# DRV8701_V2_0.net
KiCad netlist of a schematic drawn in EasyEDA Pro
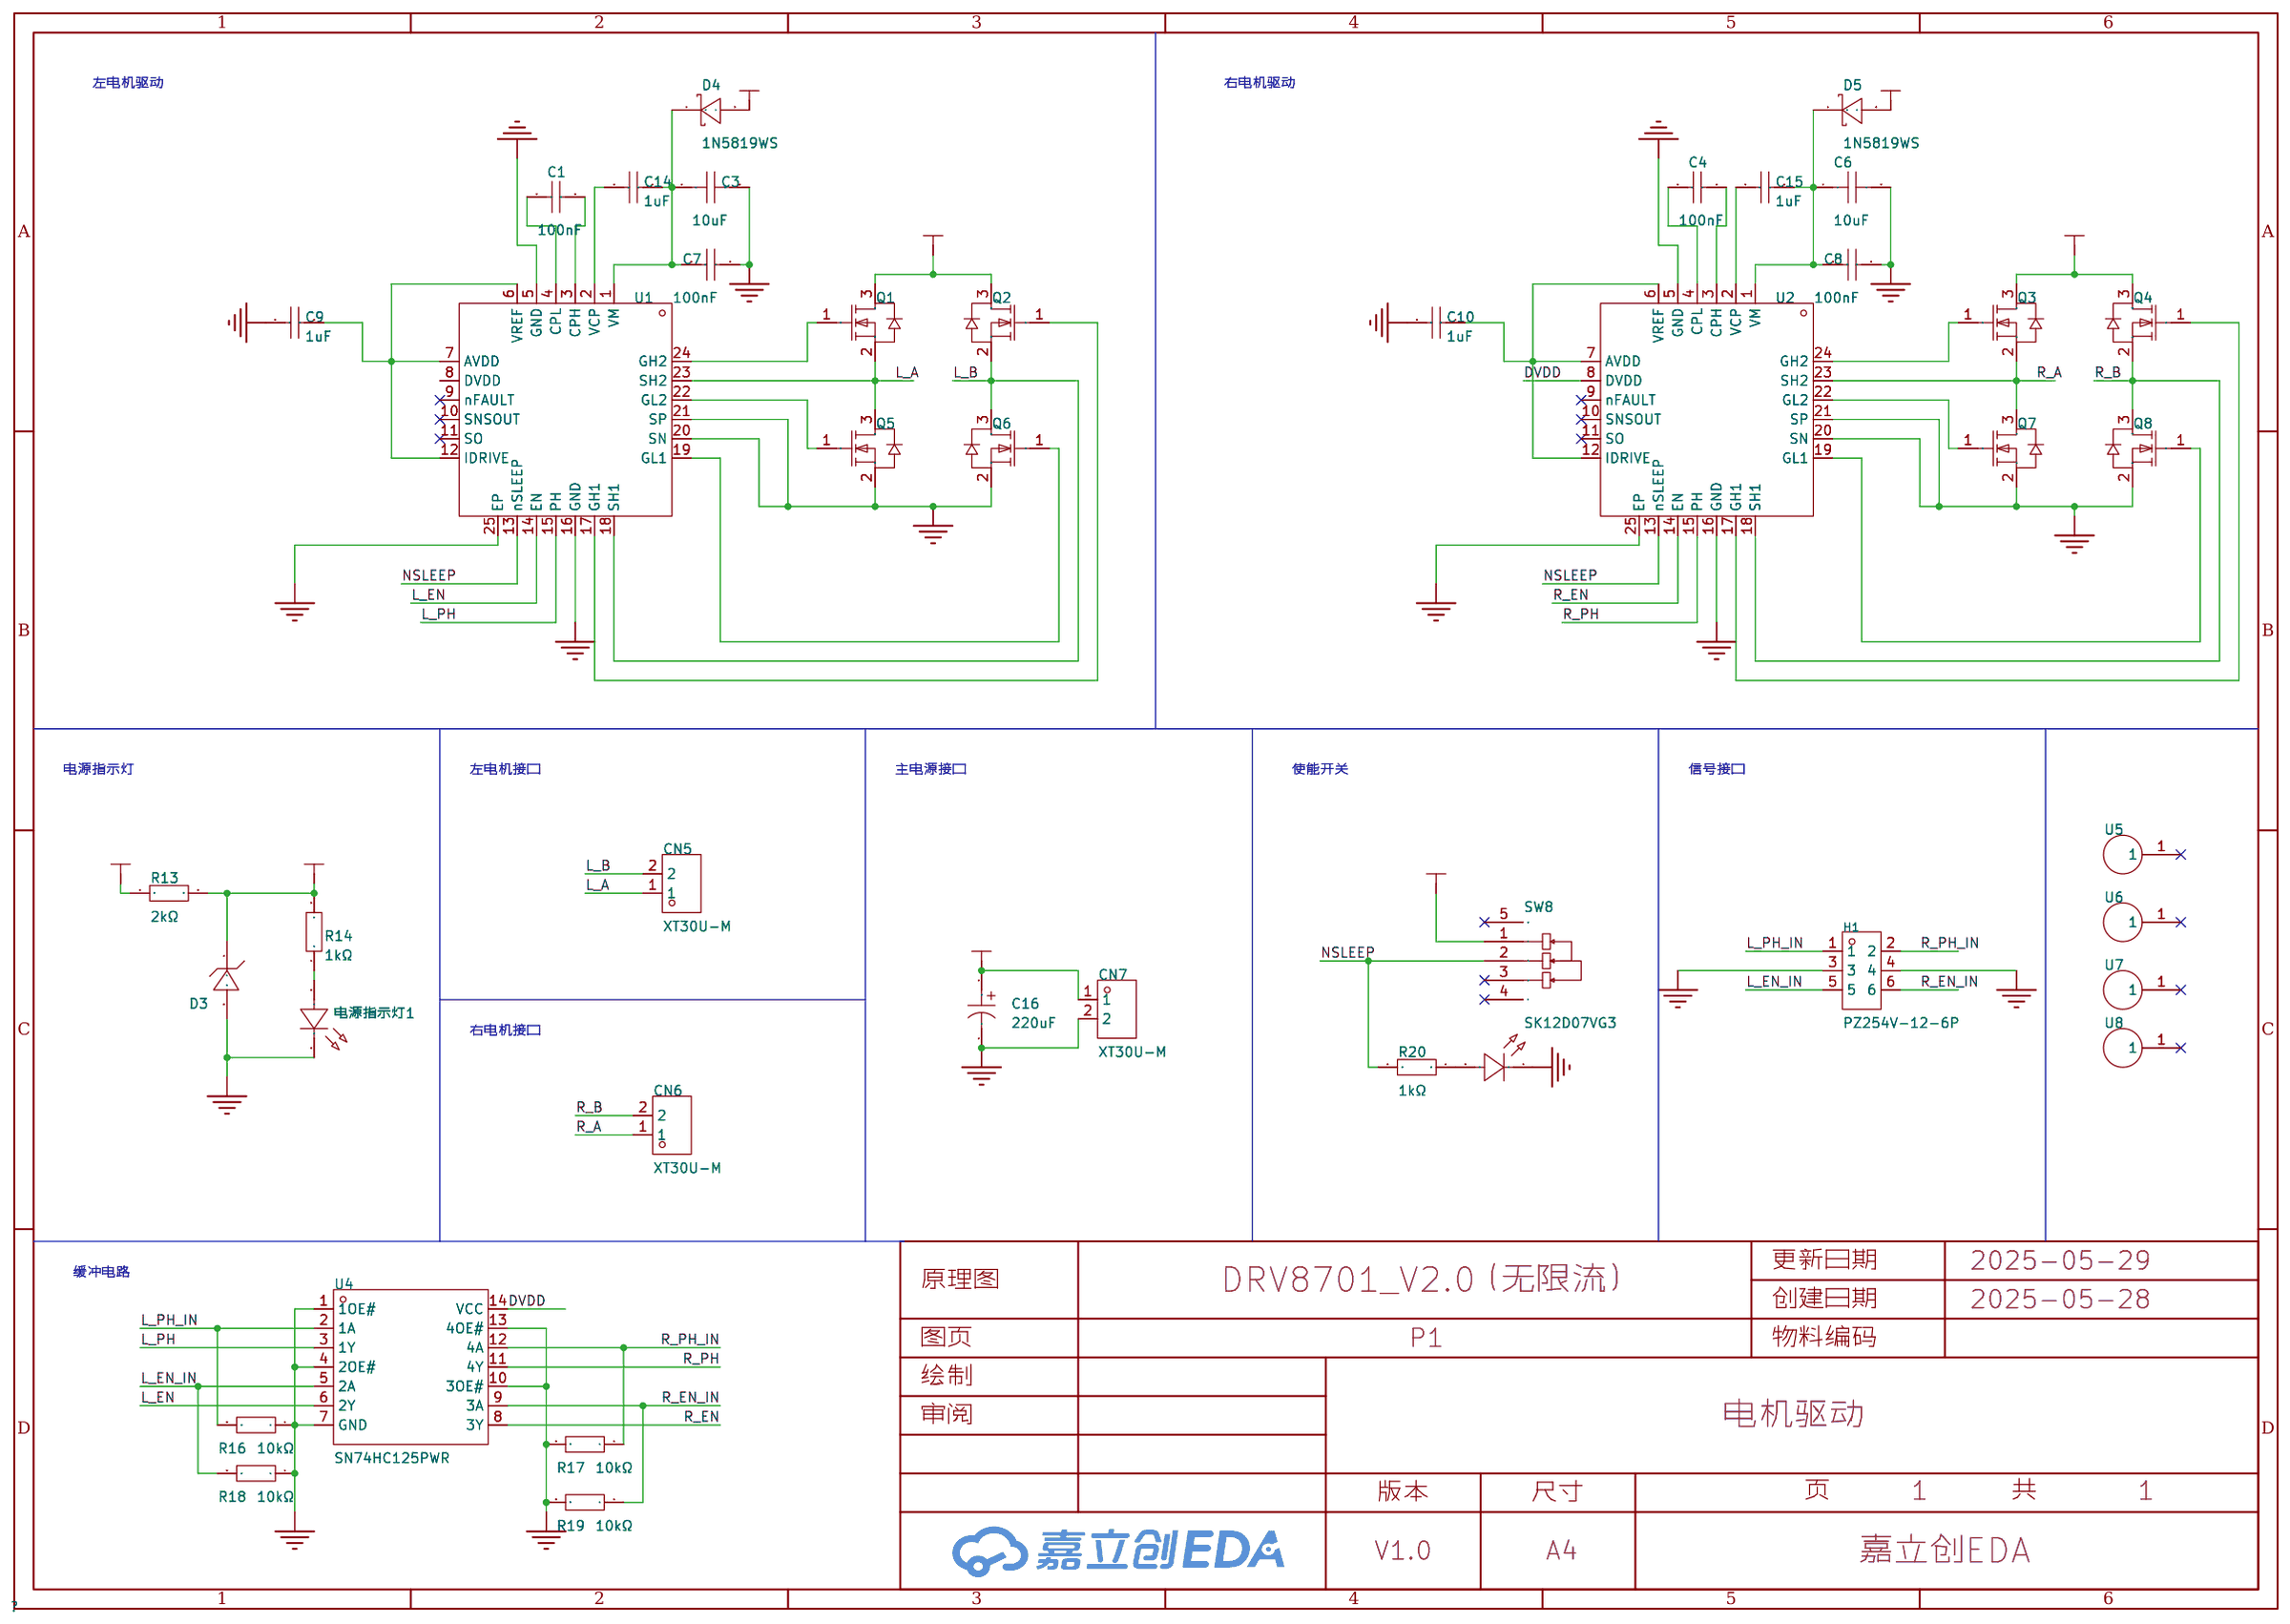
[diagram p0: schematic sheet]

(export (version "E")
  (design (tool "Eeschema 10.0.6"))
  (components
    (comp (ref "C1")
      (value "100nF")
      (footprint "easyedapro:C0603")
      (description "容值:100nF;精度:±10%;额定电压:16V;材质(温度系数):X7R;")
      (fields
        (field (name "Manufacturer Part") "CL10B104KO8NNNC")
        (field (name "Manufacturer") "SAMSUNG(三星)")
      )
      (libsource (lib "easyedapro") (part "CL10B104KO8NNNC"))
    )
    (comp (ref "C3")
      (value "10uF")
      (footprint "easyedapro:C0603")
      (description "容值:10uF;精度:±20%;额定电压:25V;材质(温度系数):X5R;")
      (fields
        (field (name "Manufacturer Part") "CL10A106MA8NRNC")
        (field (name "Manufacturer") "SAMSUNG(三星)")
      )
      (libsource (lib "easyedapro") (part "CL10A106MA8NRNC"))
    )
    (comp (ref "C4")
      (value "100nF")
      (footprint "easyedapro:C0603")
      (description "容值:100nF;精度:±10%;额定电压:16V;材质(温度系数):X7R;")
      (fields
        (field (name "Manufacturer Part") "CL10B104KO8NNNC")
        (field (name "Manufacturer") "SAMSUNG(三星)")
      )
      (libsource (lib "easyedapro") (part "CL10B104KO8NNNC"))
    )
    (comp (ref "C6")
      (value "10uF")
      (footprint "easyedapro:C0603")
      (description "容值:10uF;精度:±20%;额定电压:25V;材质(温度系数):X5R;")
      (fields
        (field (name "Manufacturer Part") "CL10A106MA8NRNC")
        (field (name "Manufacturer") "SAMSUNG(三星)")
      )
      (libsource (lib "easyedapro") (part "CL10A106MA8NRNC"))
    )
    (comp (ref "C7")
      (value "100nF")
      (footprint "easyedapro:C0603")
      (description "容值:100nF;精度:±10%;额定电压:16V;材质(温度系数):X7R;")
      (fields
        (field (name "Manufacturer Part") "CL10B104KO8NNNC")
        (field (name "Manufacturer") "SAMSUNG(三星)")
      )
      (libsource (lib "easyedapro") (part "CL10B104KO8NNNC"))
    )
    (comp (ref "C8")
      (value "100nF")
      (footprint "easyedapro:C0603")
      (description "容值:100nF;精度:±10%;额定电压:16V;材质(温度系数):X7R;")
      (fields
        (field (name "Manufacturer Part") "CL10B104KO8NNNC")
        (field (name "Manufacturer") "SAMSUNG(三星)")
      )
      (libsource (lib "easyedapro") (part "CL10B104KO8NNNC"))
    )
    (comp (ref "C9")
      (value "1uF")
      (footprint "easyedapro:C0603")
      (description "容值:1uF;精度:±10%;额定电压:25V;材质(温度系数):X7R;")
      (fields
        (field (name "Manufacturer Part") "CL10B105KA8NNNC")
        (field (name "Manufacturer") "SAMSUNG(三星)")
      )
      (libsource (lib "easyedapro") (part "CL10B105KA8NNNC"))
    )
    (comp (ref "C10")
      (value "1uF")
      (footprint "easyedapro:C0603")
      (description "容值:1uF;精度:±10%;额定电压:25V;材质(温度系数):X7R;")
      (fields
        (field (name "Manufacturer Part") "CL10B105KA8NNNC")
        (field (name "Manufacturer") "SAMSUNG(三星)")
      )
      (libsource (lib "easyedapro") (part "CL10B105KA8NNNC"))
    )
    (comp (ref "C14")
      (value "1uF")
      (footprint "easyedapro:C0603")
      (description "容值:1uF;精度:±10%;额定电压:25V;材质(温度系数):X7R;")
      (fields
        (field (name "Manufacturer Part") "CL10B105KA8NNNC")
        (field (name "Manufacturer") "SAMSUNG(三星)")
      )
      (libsource (lib "easyedapro") (part "CL10B105KA8NNNC"))
    )
    (comp (ref "C15")
      (value "1uF")
      (footprint "easyedapro:C0603")
      (description "容值:1uF;精度:±10%;额定电压:25V;材质(温度系数):X7R;")
      (fields
        (field (name "Manufacturer Part") "CL10B105KA8NNNC")
        (field (name "Manufacturer") "SAMSUNG(三星)")
      )
      (libsource (lib "easyedapro") (part "CL10B105KA8NNNC"))
    )
    (comp (ref "C16")
      (value "220uF")
      (footprint "easyedapro:CAP-TH_BD6.3-P2.50-D0.5-FD")
      (description "容值:220uF;精度:±20%;额定电压:25V;纹波电流:400mA@100kHz;等效串联电阻:180mΩ@100kHz;")
      (fields (field (name "Manufacturer Part") "03EC0593") (field (name "Manufacturer") "KNSCHA(科尼盛)"))
      (libsource (lib "easyedapro") (part "03EC0593"))
    )
    (comp (ref "CN5")
      (value "XT30U-M")
      (footprint "easyedapro:CONN-TH_XT30U-M")
      (description "类别:-;类型1:-;")
      (fields (field (name "Manufacturer") "AMASS(艾迈斯)"))
      (libsource (lib "easyedapro") (part "XT30U-M"))
    )
    (comp (ref "CN6")
      (value "XT30U-M")
      (footprint "easyedapro:CONN-TH_XT30U-M")
      (description "类别:-;类型1:-;")
      (fields (field (name "Manufacturer") "AMASS(艾迈斯)"))
      (libsource (lib "easyedapro") (part "XT30U-M"))
    )
    (comp (ref "CN7")
      (value "XT30U-M")
      (footprint "easyedapro:CONN-TH_XT30U-M")
      (description "类别:-;类型1:-;")
      (fields (field (name "Manufacturer") "AMASS(艾迈斯)"))
      (libsource (lib "easyedapro") (part "XT30U-M"))
    )
    (comp (ref "D3")
      (value "BZT52C3V3-7-F")
      (footprint "easyedapro:SOD-123_L2.7-W1.6-LS3.7-RD")
      (description "二极管配置:独立式;稳压值(标称值):3.3V;稳压值(范围):3.1V~3.5V;功率:500mW;精度:±6%;")
      (fields (field (name "Manufacturer") "DIODES(美台)"))
      (libsource (lib "easyedapro") (part "BZT52C3V3-7-F"))
    )
    (comp (ref "D4")
      (value "1N5819WS")
      (footprint "easyedapro:SOD-323_L1.8-W1.3-LS2.5-RD")
      (description "正向压降(Vf):600mV@1A;直流反向耐压(Vr):40V;整流电流:1A;")
      (fields (field (name "Manufacturer") "Hottech(合科泰)"))
      (libsource (lib "easyedapro") (part "1N5819WS"))
    )
    (comp (ref "D5")
      (value "1N5819WS")
      (footprint "easyedapro:SOD-323_L1.8-W1.3-LS2.5-RD")
      (description "正向压降(Vf):600mV@1A;直流反向耐压(Vr):40V;整流电流:1A;")
      (fields (field (name "Manufacturer") "Hottech(合科泰)"))
      (libsource (lib "easyedapro") (part "1N5819WS"))
    )
    (comp (ref "H1")
      (value "PZ254V-12-6P")
      (footprint "easyedapro:HDR-TH_6P-P2.54-V-M-R2-C3-S2.54")
      (fields (field (name "Manufacturer") "XFCN(兴飞)"))
      (libsource (lib "easyedapro") (part "PZ254V-12-6P"))
    )
    (comp (ref "Q1")
      (value "2N7002")
      (footprint "easyedapro:DSOP-8_L5.0-W5.0-P1.27-LS6.0-BL-EP（rebuild）")
      (fields (field (name "Manufacturer") "CJ(江苏长电/长晶)"))
      (libsource (lib "easyedapro") (part "TPH1R403NL(rebuild)"))
    )
    (comp (ref "Q2")
      (value "2N7002")
      (footprint "easyedapro:DSOP-8_L5.0-W5.0-P1.27-LS6.0-BL-EP（rebuild）")
      (fields (field (name "Manufacturer") "CJ(江苏长电/长晶)"))
      (libsource (lib "easyedapro") (part "TPH1R403NL(rebuild)"))
    )
    (comp (ref "Q3")
      (value "2N7002")
      (footprint "easyedapro:DSOP-8_L5.0-W5.0-P1.27-LS6.0-BL-EP（rebuild）")
      (fields (field (name "Manufacturer") "CJ(江苏长电/长晶)"))
      (libsource (lib "easyedapro") (part "TPH1R403NL(rebuild)"))
    )
    (comp (ref "Q4")
      (value "2N7002")
      (footprint "easyedapro:DSOP-8_L5.0-W5.0-P1.27-LS6.0-BL-EP（rebuild）")
      (fields (field (name "Manufacturer") "CJ(江苏长电/长晶)"))
      (libsource (lib "easyedapro") (part "TPH1R403NL(rebuild)"))
    )
    (comp (ref "Q5")
      (value "2N7002")
      (footprint "easyedapro:DSOP-8_L5.0-W5.0-P1.27-LS6.0-BL-EP（rebuild）")
      (fields (field (name "Manufacturer") "CJ(江苏长电/长晶)"))
      (libsource (lib "easyedapro") (part "TPH1R403NL(rebuild)"))
    )
    (comp (ref "Q6")
      (value "2N7002")
      (footprint "easyedapro:DSOP-8_L5.0-W5.0-P1.27-LS6.0-BL-EP（rebuild）")
      (fields (field (name "Manufacturer") "CJ(江苏长电/长晶)"))
      (libsource (lib "easyedapro") (part "TPH1R403NL(rebuild)"))
    )
    (comp (ref "Q7")
      (value "2N7002")
      (footprint "easyedapro:DSOP-8_L5.0-W5.0-P1.27-LS6.0-BL-EP（rebuild）")
      (fields (field (name "Manufacturer") "CJ(江苏长电/长晶)"))
      (libsource (lib "easyedapro") (part "TPH1R403NL(rebuild)"))
    )
    (comp (ref "Q8")
      (value "2N7002")
      (footprint "easyedapro:DSOP-8_L5.0-W5.0-P1.27-LS6.0-BL-EP（rebuild）")
      (fields (field (name "Manufacturer") "CJ(江苏长电/长晶)"))
      (libsource (lib "easyedapro") (part "TPH1R403NL(rebuild)"))
    )
    (comp (ref "R13")
      (value "2kΩ")
      (footprint "easyedapro:R0603")
      (description "电阻类型:厚膜电阻;阻值:2.2kΩ;精度:±1%;功率:100mW;最大工作电压:75V;温度系数:±100ppm/°C;")
      (fields
        (field (name "Manufacturer Part") "0603WAF2201T5E")
        (field (name "Manufacturer") "UNI-ROYAL(厚声)")
      )
      (libsource (lib "easyedapro") (part "0603WAF2201T5E"))
    )
    (comp (ref "R14")
      (value "1kΩ")
      (footprint "easyedapro:R0603")
      (description "电阻类型:厚膜电阻;阻值:1kΩ;精度:±1%;功率:100mW;最大工作电压:75V;温度系数:±100ppm/°C;")
      (fields
        (field (name "Manufacturer Part") "0603WAF1001T5E")
        (field (name "Manufacturer") "UNI-ROYAL(厚声)")
      )
      (libsource (lib "easyedapro") (part "0603WAF1001T5E"))
    )
    (comp (ref "R16")
      (value "10kΩ")
      (footprint "easyedapro:R0603")
      (description "电阻类型:厚膜电阻;阻值:10kΩ;精度:±1%;功率:100mW;最大工作电压:75V;温度系数:±100ppm/°C;")
      (fields
        (field (name "Manufacturer Part") "0603WAF1002T5E")
        (field (name "Manufacturer") "UNI-ROYAL(厚声)")
      )
      (libsource (lib "easyedapro") (part "0603WAF1002T5E"))
    )
    (comp (ref "R17")
      (value "10kΩ")
      (footprint "easyedapro:R0603")
      (description "电阻类型:厚膜电阻;阻值:10kΩ;精度:±1%;功率:100mW;最大工作电压:75V;温度系数:±100ppm/°C;")
      (fields
        (field (name "Manufacturer Part") "0603WAF1002T5E")
        (field (name "Manufacturer") "UNI-ROYAL(厚声)")
      )
      (libsource (lib "easyedapro") (part "0603WAF1002T5E"))
    )
    (comp (ref "R18")
      (value "10kΩ")
      (footprint "easyedapro:R0603")
      (description "电阻类型:厚膜电阻;阻值:10kΩ;精度:±1%;功率:100mW;最大工作电压:75V;温度系数:±100ppm/°C;")
      (fields
        (field (name "Manufacturer Part") "0603WAF1002T5E")
        (field (name "Manufacturer") "UNI-ROYAL(厚声)")
      )
      (libsource (lib "easyedapro") (part "0603WAF1002T5E"))
    )
    (comp (ref "R19")
      (value "10kΩ")
      (footprint "easyedapro:R0603")
      (description "电阻类型:厚膜电阻;阻值:10kΩ;精度:±1%;功率:100mW;最大工作电压:75V;温度系数:±100ppm/°C;")
      (fields
        (field (name "Manufacturer Part") "0603WAF1002T5E")
        (field (name "Manufacturer") "UNI-ROYAL(厚声)")
      )
      (libsource (lib "easyedapro") (part "0603WAF1002T5E"))
    )
    (comp (ref "R20")
      (value "1kΩ")
      (footprint "easyedapro:R0603")
      (description "电阻类型:厚膜电阻;阻值:1kΩ;精度:±1%;功率:100mW;最大工作电压:75V;温度系数:±100ppm/°C;")
      (fields
        (field (name "Manufacturer Part") "0603WAF1001T5E")
        (field (name "Manufacturer") "UNI-ROYAL(厚声)")
      )
      (libsource (lib "easyedapro") (part "0603WAF1001T5E"))
    )
    (comp (ref "SW8")
      (value "SK12D07VG3")
      (footprint "easyedapro:SW-TH_SK12D07VG3")
      (description "电路结构:单刀双掷;安装方式:侧插;开关颜色:-;额定电流(DC):500mA;额定电压(DC):50V;额定电流(AC):-;额定电压(AC):-;机械寿命:5千次;")
      (fields (field (name "Manufacturer") "SHOU HAN(首韩)"))
      (libsource (lib "easyedapro") (part "SK12D07VG3_C431547"))
    )
    (comp (ref "U1")
      (value "DRV8701ERGET")
      (footprint "easyedapro:VQFN-24_L4.0-W4.0-P0.50-BL-EP2.5")
      (description "DRV8701 47V H 桥智能栅极驱动器")
      (fields (field (name "Manufacturer") "TI(德州仪器)"))
      (libsource (lib "easyedapro") (part "DRV8701ERGET"))
    )
    (comp (ref "U2")
      (value "DRV8701ERGET")
      (footprint "easyedapro:VQFN-24_L4.0-W4.0-P0.50-BL-EP2.5")
      (description "DRV8701 47V H 桥智能栅极驱动器")
      (fields (field (name "Manufacturer") "TI(德州仪器)"))
      (libsource (lib "easyedapro") (part "DRV8701ERGET"))
    )
    (comp (ref "U4")
      (value "SN74HC125PWR")
      (footprint "easyedapro:TSSOP-14_L5.0-W4.4-P0.65-LS6.5-BL")
      (description "输入类型:-;电源电压:2V~6V;元件数:4;每个元件位数:1;灌电流(IOL):7.8mA;拉电流(IOH):7.8mA;")
      (fields (field (name "Manufacturer") "TI(德州仪器)"))
      (libsource (lib "easyedapro") (part "SN74HC125PWR"))
    )
    (comp (ref "U5") (value "~") (footprint "easyedapro:M3螺丝孔") (libsource (lib "easyedapro") (part "M3螺丝孔")))
    (comp (ref "U6") (value "~") (footprint "easyedapro:M3螺丝孔") (libsource (lib "easyedapro") (part "M3螺丝孔")))
    (comp (ref "U7") (value "~") (footprint "easyedapro:M3螺丝孔") (libsource (lib "easyedapro") (part "M3螺丝孔")))
    (comp (ref "U8") (value "~") (footprint "easyedapro:M3螺丝孔") (libsource (lib "easyedapro") (part "M3螺丝孔")))
    (comp (ref "电源指示灯1")
      (value "XL-1608SURC-06")
      (footprint "easyedapro:LED0603-RD_RED")
      (description "发光颜色:红色;功率:55mW;正向电流:25mA;主波长:617nm~621nm;透镜颜色:无色透明透镜;色温:-;发光角度:120°;载带方式:正贴;工作温度:-30°C~+85°C;")
      (fields (field (name "Manufacturer") "XINGLIGHT(成兴光)"))
      (libsource (lib "easyedapro") (part "XL-1608SURC-06"))
    )
    (comp (ref "电源指示灯2")
      (value "XL-1608SURC-06")
      (footprint "easyedapro:LED0603-RD_RED")
      (description "发光颜色:红色;功率:55mW;正向电流:25mA;主波长:617nm~621nm;透镜颜色:无色透明透镜;色温:-;发光角度:120°;载带方式:正贴;工作温度:-30°C~+85°C;")
      (fields (field (name "Manufacturer") "XINGLIGHT(成兴光)"))
      (libsource (lib "easyedapro") (part "XL-1608SURC-06"))
    )
  )
  (nets
    (net (code "1") (name "/DVDD") (class "Default")
      (node (ref "U2") (pin "8") (pinfunction "DVDD_8") (pintype "unspecified"))
      (node (ref "U4") (pin "14") (pinfunction "VCC_14") (pintype "unspecified"))
    )
    (net (code "2") (name "/L_A") (class "Default")
      (node (ref "CN5") (pin "1") (pinfunction "1_1") (pintype "unspecified"))
      (node (ref "Q1") (pin "2") (pinfunction "S_2") (pintype "unspecified"))
      (node (ref "Q5") (pin "3") (pinfunction "D_3") (pintype "unspecified"))
      (node (ref "U1") (pin "23") (pinfunction "SH2_23") (pintype "unspecified"))
    )
    (net (code "3") (name "/L_B") (class "Default")
      (node (ref "CN5") (pin "2") (pinfunction "2_2") (pintype "unspecified"))
      (node (ref "Q2") (pin "2") (pinfunction "S_2") (pintype "unspecified"))
      (node (ref "Q6") (pin "3") (pinfunction "D_3") (pintype "unspecified"))
      (node (ref "U1") (pin "18") (pinfunction "SH1_18") (pintype "unspecified"))
    )
    (net (code "4") (name "/L_EN") (class "Default")
      (node (ref "U1") (pin "14") (pinfunction "EN_14") (pintype "unspecified"))
      (node (ref "U4") (pin "6") (pinfunction "2Y_6") (pintype "unspecified"))
    )
    (net (code "5") (name "/L_EN_IN") (class "Default")
      (node (ref "H1") (pin "5") (pinfunction "5_5") (pintype "input"))
      (node (ref "R18") (pin "2") (pinfunction "2_2") (pintype "input"))
      (node (ref "U4") (pin "5") (pinfunction "2A_5") (pintype "unspecified"))
    )
    (net (code "6") (name "/L_PH") (class "Default")
      (node (ref "U1") (pin "15") (pinfunction "PH_15") (pintype "unspecified"))
      (node (ref "U4") (pin "3") (pinfunction "1Y_3") (pintype "unspecified"))
    )
    (net (code "7") (name "/L_PH_IN") (class "Default")
      (node (ref "H1") (pin "1") (pinfunction "1_1") (pintype "input"))
      (node (ref "R16") (pin "2") (pinfunction "2_2") (pintype "input"))
      (node (ref "U4") (pin "2") (pinfunction "1A_2") (pintype "unspecified"))
    )
    (net (code "8") (name "/NSLEEP") (class "Default")
      (node (ref "R20") (pin "2") (pinfunction "2_2") (pintype "input"))
      (node (ref "SW8") (pin "2") (pinfunction "2_2") (pintype "unspecified"))
      (node (ref "U1") (pin "13") (pinfunction "nSLEEP_13") (pintype "unspecified"))
      (node (ref "U2") (pin "13") (pinfunction "nSLEEP_13") (pintype "unspecified"))
    )
    (net (code "9") (name "/R_A") (class "Default")
      (node (ref "CN6") (pin "1") (pinfunction "1_1") (pintype "unspecified"))
      (node (ref "Q3") (pin "2") (pinfunction "S_2") (pintype "unspecified"))
      (node (ref "Q7") (pin "3") (pinfunction "D_3") (pintype "unspecified"))
      (node (ref "U2") (pin "23") (pinfunction "SH2_23") (pintype "unspecified"))
    )
    (net (code "10") (name "/R_B") (class "Default")
      (node (ref "CN6") (pin "2") (pinfunction "2_2") (pintype "unspecified"))
      (node (ref "Q4") (pin "2") (pinfunction "S_2") (pintype "unspecified"))
      (node (ref "Q8") (pin "3") (pinfunction "D_3") (pintype "unspecified"))
      (node (ref "U2") (pin "18") (pinfunction "SH1_18") (pintype "unspecified"))
    )
    (net (code "11") (name "/R_EN") (class "Default")
      (node (ref "U2") (pin "14") (pinfunction "EN_14") (pintype "unspecified"))
      (node (ref "U4") (pin "8") (pinfunction "3Y_8") (pintype "unspecified"))
    )
    (net (code "12") (name "/R_EN_IN") (class "Default")
      (node (ref "H1") (pin "6") (pinfunction "6_6") (pintype "input"))
      (node (ref "R19") (pin "1") (pinfunction "1_1") (pintype "input"))
      (node (ref "U4") (pin "9") (pinfunction "3A_9") (pintype "unspecified"))
    )
    (net (code "13") (name "/R_PH") (class "Default")
      (node (ref "U2") (pin "15") (pinfunction "PH_15") (pintype "unspecified"))
      (node (ref "U4") (pin "11") (pinfunction "4Y_11") (pintype "unspecified"))
    )
    (net (code "14") (name "/R_PH_IN") (class "Default")
      (node (ref "H1") (pin "2") (pinfunction "2_2") (pintype "input"))
      (node (ref "R17") (pin "1") (pinfunction "1_1") (pintype "input"))
      (node (ref "U4") (pin "12") (pinfunction "4A_12") (pintype "unspecified"))
    )
    (net (code "15") (name "3.3V") (class "Default")
      (node (ref "D3") (pin "1") (pinfunction "K_1") (pintype "unspecified"))
      (node (ref "R13") (pin "2") (pinfunction "2_2") (pintype "input"))
      (node (ref "R14") (pin "2") (pinfunction "2_2") (pintype "input"))
      (node (ref "SW8") (pin "1") (pinfunction "1_1") (pintype "unspecified"))
    )
    (net (code "16") (name "GND") (class "Default")
      (node (ref "C10") (pin "2") (pinfunction "2_2") (pintype "input"))
      (node (ref "C16") (pin "2") (pinfunction "2_2") (pintype "input"))
      (node (ref "C3") (pin "2") (pinfunction "2_2") (pintype "unspecified"))
      (node (ref "C6") (pin "2") (pinfunction "2_2") (pintype "unspecified"))
      (node (ref "C7") (pin "1") (pinfunction "1_1") (pintype "input"))
      (node (ref "C8") (pin "1") (pinfunction "1_1") (pintype "input"))
      (node (ref "C9") (pin "2") (pinfunction "2_2") (pintype "input"))
      (node (ref "CN7") (pin "2") (pinfunction "2_2") (pintype "unspecified"))
      (node (ref "D3") (pin "2") (pinfunction "A_2") (pintype "unspecified"))
      (node (ref "H1") (pin "3") (pinfunction "3_3") (pintype "input"))
      (node (ref "H1") (pin "4") (pinfunction "4_4") (pintype "input"))
      (node (ref "Q5") (pin "2") (pinfunction "S_2") (pintype "unspecified"))
      (node (ref "Q6") (pin "2") (pinfunction "S_2") (pintype "unspecified"))
      (node (ref "Q7") (pin "2") (pinfunction "S_2") (pintype "unspecified"))
      (node (ref "Q8") (pin "2") (pinfunction "S_2") (pintype "unspecified"))
      (node (ref "R16") (pin "1") (pinfunction "1_1") (pintype "input"))
      (node (ref "R17") (pin "2") (pinfunction "2_2") (pintype "input"))
      (node (ref "R18") (pin "1") (pinfunction "1_1") (pintype "input"))
      (node (ref "R19") (pin "2") (pinfunction "2_2") (pintype "input"))
      (node (ref "U1") (pin "16") (pinfunction "GND_16") (pintype "unspecified"))
      (node (ref "U1") (pin "20") (pinfunction "SN_20") (pintype "unspecified"))
      (node (ref "U1") (pin "21") (pinfunction "SP_21") (pintype "unspecified"))
      (node (ref "U1") (pin "25") (pinfunction "EP_25") (pintype "unspecified"))
      (node (ref "U1") (pin "5") (pinfunction "GND_5") (pintype "unspecified"))
      (node (ref "U2") (pin "16") (pinfunction "GND_16") (pintype "unspecified"))
      (node (ref "U2") (pin "20") (pinfunction "SN_20") (pintype "unspecified"))
      (node (ref "U2") (pin "21") (pinfunction "SP_21") (pintype "unspecified"))
      (node (ref "U2") (pin "25") (pinfunction "EP_25") (pintype "unspecified"))
      (node (ref "U2") (pin "5") (pinfunction "GND_5") (pintype "unspecified"))
      (node (ref "U4") (pin "1") (pinfunction "1OE#_1") (pintype "unspecified"))
      (node (ref "U4") (pin "10") (pinfunction "3OE#_10") (pintype "unspecified"))
      (node (ref "U4") (pin "13") (pinfunction "4OE#_13") (pintype "unspecified"))
      (node (ref "U4") (pin "4") (pinfunction "2OE#_4") (pintype "unspecified"))
      (node (ref "U4") (pin "7") (pinfunction "GND_7") (pintype "unspecified"))
      (node (ref "电源指示灯1") (pin "1") (pinfunction "K_1") (pintype "unspecified"))
      (node (ref "电源指示灯2") (pin "1") (pinfunction "K_1") (pintype "unspecified"))
    )
    (net (code "17") (name "Net-(D4-K)") (class "Default")
      (node (ref "C14") (pin "1") (pinfunction "1_1") (pintype "input"))
      (node (ref "C3") (pin "1") (pinfunction "1_1") (pintype "unspecified"))
      (node (ref "C7") (pin "2") (pinfunction "2_2") (pintype "input"))
      (node (ref "D4") (pin "1") (pinfunction "K_1") (pintype "unspecified"))
      (node (ref "U1") (pin "1") (pinfunction "VM_1") (pintype "unspecified"))
    )
    (net (code "18") (name "Net-(D5-K)") (class "Default")
      (node (ref "C15") (pin "1") (pinfunction "1_1") (pintype "input"))
      (node (ref "C6") (pin "1") (pinfunction "1_1") (pintype "unspecified"))
      (node (ref "C8") (pin "2") (pinfunction "2_2") (pintype "input"))
      (node (ref "D5") (pin "1") (pinfunction "K_1") (pintype "unspecified"))
      (node (ref "U2") (pin "1") (pinfunction "VM_1") (pintype "unspecified"))
    )
    (net (code "19") (name "Net-(Q1-G)") (class "Default")
      (node (ref "Q1") (pin "1") (pinfunction "G_1") (pintype "unspecified"))
      (node (ref "U1") (pin "24") (pinfunction "GH2_24") (pintype "unspecified"))
    )
    (net (code "20") (name "Net-(Q2-G)") (class "Default")
      (node (ref "Q2") (pin "1") (pinfunction "G_1") (pintype "unspecified"))
      (node (ref "U1") (pin "17") (pinfunction "GH1_17") (pintype "unspecified"))
    )
    (net (code "21") (name "Net-(Q3-G)") (class "Default")
      (node (ref "Q3") (pin "1") (pinfunction "G_1") (pintype "unspecified"))
      (node (ref "U2") (pin "24") (pinfunction "GH2_24") (pintype "unspecified"))
    )
    (net (code "22") (name "Net-(Q4-G)") (class "Default")
      (node (ref "Q4") (pin "1") (pinfunction "G_1") (pintype "unspecified"))
      (node (ref "U2") (pin "17") (pinfunction "GH1_17") (pintype "unspecified"))
    )
    (net (code "23") (name "Net-(Q5-G)") (class "Default")
      (node (ref "Q5") (pin "1") (pinfunction "G_1") (pintype "unspecified"))
      (node (ref "U1") (pin "22") (pinfunction "GL2_22") (pintype "unspecified"))
    )
    (net (code "24") (name "Net-(Q6-G)") (class "Default")
      (node (ref "Q6") (pin "1") (pinfunction "G_1") (pintype "unspecified"))
      (node (ref "U1") (pin "19") (pinfunction "GL1_19") (pintype "unspecified"))
    )
    (net (code "25") (name "Net-(Q7-G)") (class "Default")
      (node (ref "Q7") (pin "1") (pinfunction "G_1") (pintype "unspecified"))
      (node (ref "U2") (pin "22") (pinfunction "GL2_22") (pintype "unspecified"))
    )
    (net (code "26") (name "Net-(Q8-G)") (class "Default")
      (node (ref "Q8") (pin "1") (pinfunction "G_1") (pintype "unspecified"))
      (node (ref "U2") (pin "19") (pinfunction "GL1_19") (pintype "unspecified"))
    )
    (net (code "27") (name "Net-(U1-AVDD)") (class "Default")
      (node (ref "C9") (pin "1") (pinfunction "1_1") (pintype "input"))
      (node (ref "U1") (pin "12") (pinfunction "IDRIVE_12") (pintype "unspecified"))
      (node (ref "U1") (pin "6") (pinfunction "VREF_6") (pintype "unspecified"))
      (node (ref "U1") (pin "7") (pinfunction "AVDD_7") (pintype "unspecified"))
    )
    (net (code "28") (name "Net-(U1-CPH)") (class "Default")
      (node (ref "C1") (pin "1") (pinfunction "1_1") (pintype "input"))
      (node (ref "U1") (pin "3") (pinfunction "CPH_3") (pintype "unspecified"))
    )
    (net (code "29") (name "Net-(U1-CPL)") (class "Default")
      (node (ref "C1") (pin "2") (pinfunction "2_2") (pintype "input"))
      (node (ref "U1") (pin "4") (pinfunction "CPL_4") (pintype "unspecified"))
    )
    (net (code "30") (name "Net-(U1-VCP)") (class "Default")
      (node (ref "C14") (pin "2") (pinfunction "2_2") (pintype "input"))
      (node (ref "U1") (pin "2") (pinfunction "VCP_2") (pintype "unspecified"))
    )
    (net (code "31") (name "Net-(U2-AVDD)") (class "Default")
      (node (ref "C10") (pin "1") (pinfunction "1_1") (pintype "input"))
      (node (ref "U2") (pin "12") (pinfunction "IDRIVE_12") (pintype "unspecified"))
      (node (ref "U2") (pin "6") (pinfunction "VREF_6") (pintype "unspecified"))
      (node (ref "U2") (pin "7") (pinfunction "AVDD_7") (pintype "unspecified"))
    )
    (net (code "32") (name "Net-(U2-CPH)") (class "Default")
      (node (ref "C4") (pin "1") (pinfunction "1_1") (pintype "input"))
      (node (ref "U2") (pin "3") (pinfunction "CPH_3") (pintype "unspecified"))
    )
    (net (code "33") (name "Net-(U2-CPL)") (class "Default")
      (node (ref "C4") (pin "2") (pinfunction "2_2") (pintype "input"))
      (node (ref "U2") (pin "4") (pinfunction "CPL_4") (pintype "unspecified"))
    )
    (net (code "34") (name "Net-(U2-VCP)") (class "Default")
      (node (ref "C15") (pin "2") (pinfunction "2_2") (pintype "input"))
      (node (ref "U2") (pin "2") (pinfunction "VCP_2") (pintype "unspecified"))
    )
    (net (code "35") (name "Net-(电源指示灯1-A)") (class "Default")
      (node (ref "R14") (pin "1") (pinfunction "1_1") (pintype "input"))
      (node (ref "电源指示灯1") (pin "2") (pinfunction "A_2") (pintype "unspecified"))
    )
    (net (code "36") (name "Net-(电源指示灯2-A)") (class "Default")
      (node (ref "R20") (pin "1") (pinfunction "1_1") (pintype "input"))
      (node (ref "电源指示灯2") (pin "2") (pinfunction "A_2") (pintype "unspecified"))
    )
    (net (code "37") (name "VM") (class "Default")
      (node (ref "C16") (pin "1") (pinfunction "1_1") (pintype "input"))
      (node (ref "CN7") (pin "1") (pinfunction "1_1") (pintype "unspecified"))
      (node (ref "D4") (pin "2") (pinfunction "A_2") (pintype "unspecified"))
      (node (ref "D5") (pin "2") (pinfunction "A_2") (pintype "unspecified"))
      (node (ref "Q1") (pin "3") (pinfunction "D_3") (pintype "unspecified"))
      (node (ref "Q2") (pin "3") (pinfunction "D_3") (pintype "unspecified"))
      (node (ref "Q3") (pin "3") (pinfunction "D_3") (pintype "unspecified"))
      (node (ref "Q4") (pin "3") (pinfunction "D_3") (pintype "unspecified"))
      (node (ref "R13") (pin "1") (pinfunction "1_1") (pintype "input"))
    )
    (net (code "38") (name "unconnected-(SW8-Pad3)") (class "Default")
      (node (ref "SW8") (pin "3") (pinfunction "3_3") (pintype "unspecified+no_connect"))
    )
    (net (code "39") (name "unconnected-(SW8-Pad4)") (class "Default")
      (node (ref "SW8") (pin "4") (pinfunction "4_4") (pintype "unspecified+no_connect"))
    )
    (net (code "40") (name "unconnected-(SW8-Pad5)") (class "Default")
      (node (ref "SW8") (pin "5") (pinfunction "5_5") (pintype "unspecified+no_connect"))
    )
    (net (code "41") (name "unconnected-(U1-DVDD-Pad8)") (class "Default")
      (node (ref "U1") (pin "8") (pinfunction "DVDD_8") (pintype "unspecified"))
    )
    (net (code "42") (name "unconnected-(U1-SNSOUT-Pad10)") (class "Default")
      (node (ref "U1") (pin "10") (pinfunction "SNSOUT_10") (pintype "unspecified+no_connect"))
    )
    (net (code "43") (name "unconnected-(U1-SO-Pad11)") (class "Default")
      (node (ref "U1") (pin "11") (pinfunction "SO_11") (pintype "unspecified+no_connect"))
    )
    (net (code "44") (name "unconnected-(U1-nFAULT-Pad9)") (class "Default")
      (node (ref "U1") (pin "9") (pinfunction "nFAULT_9") (pintype "unspecified+no_connect"))
    )
    (net (code "45") (name "unconnected-(U2-SNSOUT-Pad10)") (class "Default")
      (node (ref "U2") (pin "10") (pinfunction "SNSOUT_10") (pintype "unspecified+no_connect"))
    )
    (net (code "46") (name "unconnected-(U2-SO-Pad11)") (class "Default")
      (node (ref "U2") (pin "11") (pinfunction "SO_11") (pintype "unspecified+no_connect"))
    )
    (net (code "47") (name "unconnected-(U2-nFAULT-Pad9)") (class "Default")
      (node (ref "U2") (pin "9") (pinfunction "nFAULT_9") (pintype "unspecified+no_connect"))
    )
    (net (code "48") (name "unconnected-(U5-Pad1)") (class "Default")
      (node (ref "U5") (pin "1") (pinfunction "1_1") (pintype "input+no_connect"))
    )
    (net (code "49") (name "unconnected-(U6-Pad1)") (class "Default")
      (node (ref "U6") (pin "1") (pinfunction "1_1") (pintype "input+no_connect"))
    )
    (net (code "50") (name "unconnected-(U7-Pad1)") (class "Default")
      (node (ref "U7") (pin "1") (pinfunction "1_1") (pintype "input+no_connect"))
    )
    (net (code "51") (name "unconnected-(U8-Pad1)") (class "Default")
      (node (ref "U8") (pin "1") (pinfunction "1_1") (pintype "input+no_connect"))
    )
  )
)
